# board.net
KiCad netlist of a schematic drawn in EAGLE
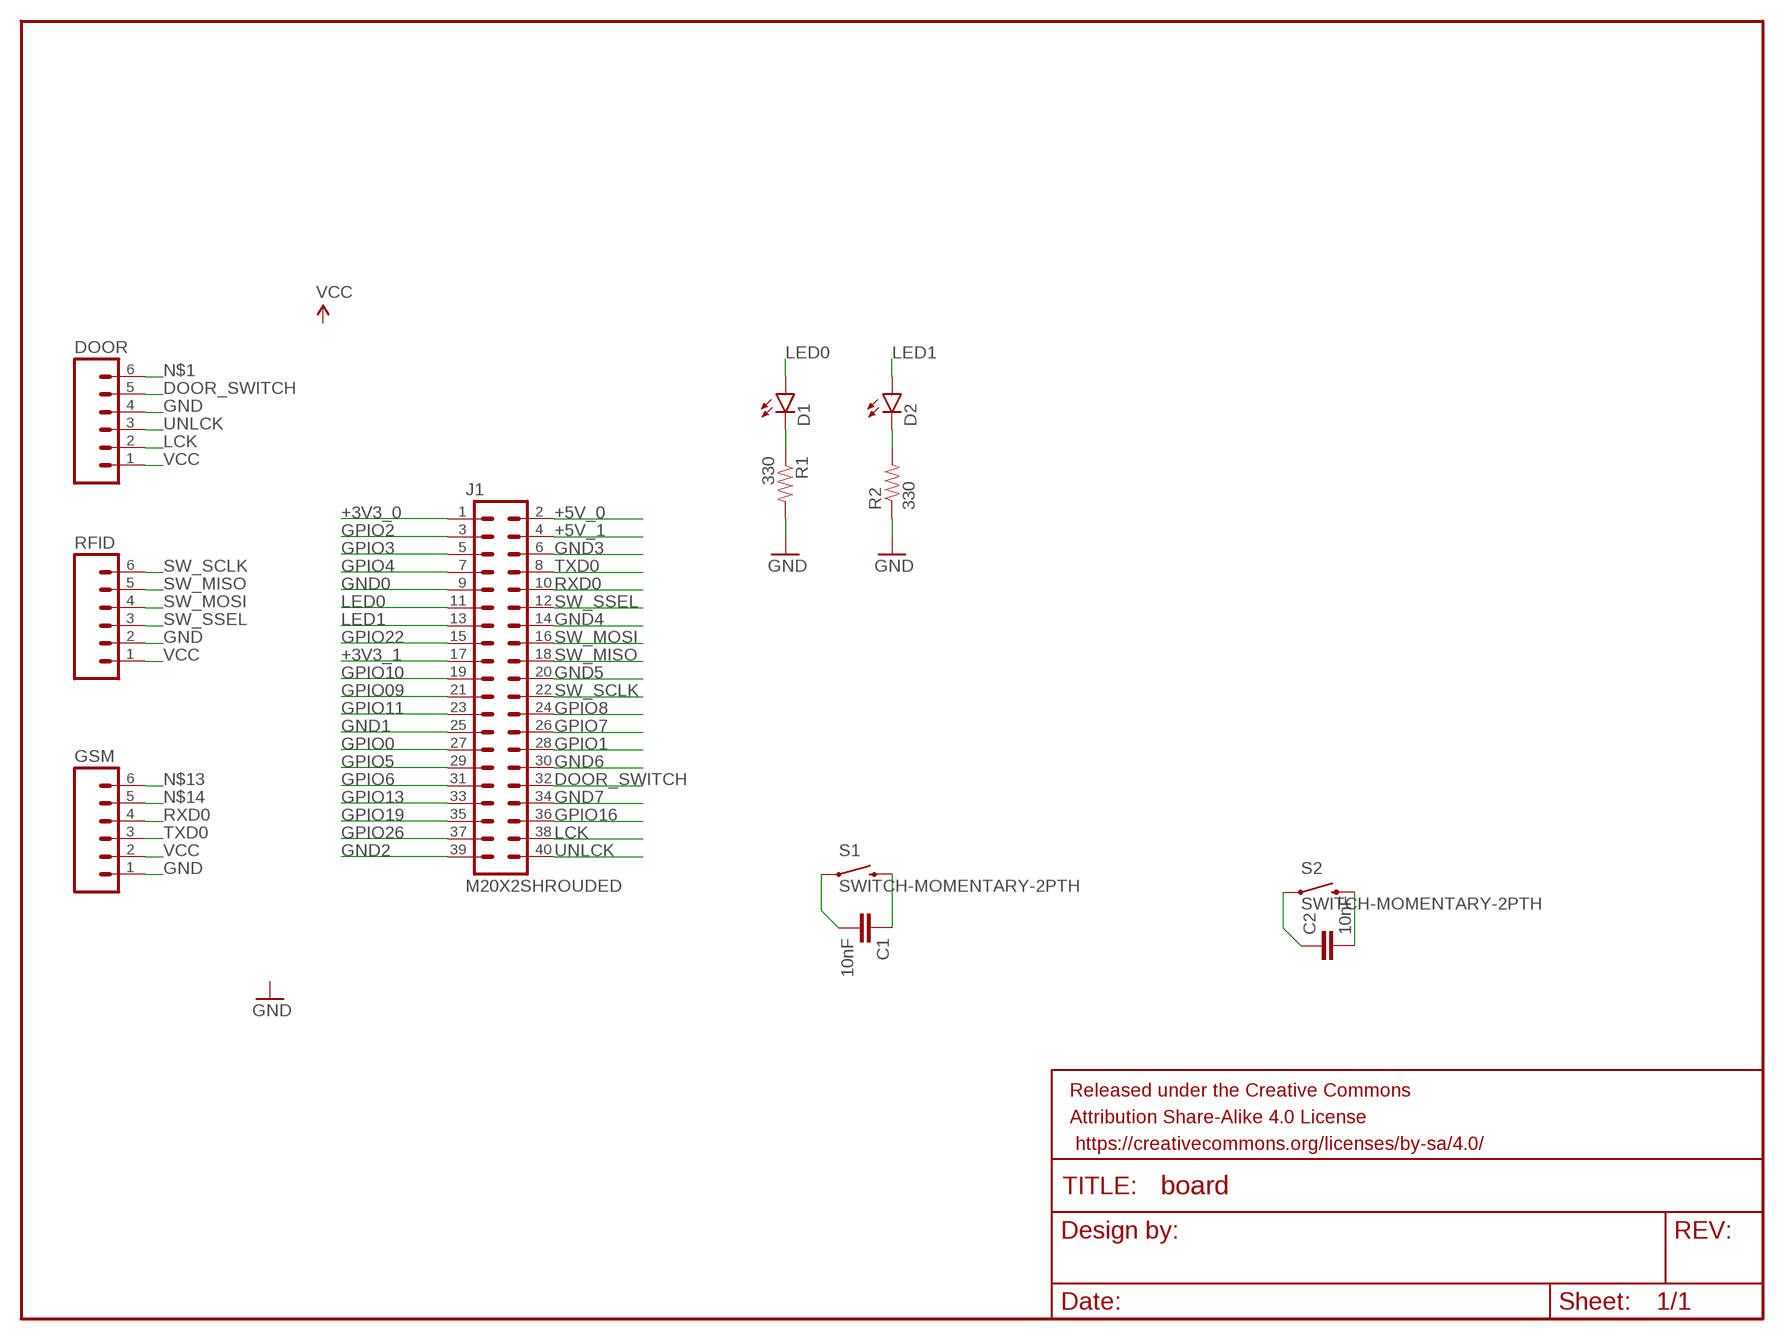
[diagram p0: schematic, sheet 1]

(export (version "E")
  (design (tool "Eeschema 10.0.6"))
  (components
    (comp (ref "C1")
      (value "10nF")
      (footprint "eagle-import:CAP-PTH-SMALL")
      (libsource (lib "eagle-import") (part "CAPPTH"))
    )
    (comp (ref "C2")
      (value "10nF")
      (footprint "eagle-import:CAP-PTH-SMALL")
      (libsource (lib "eagle-import") (part "CAPPTH"))
    )
    (comp (ref "D1")
      (value "LED5MM")
      (footprint "eagle-import:LED5MM")
      (libsource (lib "eagle-import") (part "LED5MM"))
    )
    (comp (ref "D2")
      (value "LED5MM")
      (footprint "eagle-import:LED5MM")
      (libsource (lib "eagle-import") (part "LED5MM"))
    )
    (comp (ref "DOOR")
      (value "M06LOCK")
      (footprint "eagle-import:1X06_LOCK")
      (libsource (lib "eagle-import") (part "M06LOCK"))
    )
    (comp (ref "FRAME1")
      (value "FRAME-LETTER")
      (footprint "eagle-import:CREATIVE_COMMONS")
      (libsource (lib "eagle-import") (part "FRAME-LETTER"))
    )
    (comp (ref "GSM")
      (value "M06LOCK")
      (footprint "eagle-import:1X06_LOCK")
      (libsource (lib "eagle-import") (part "M06LOCK"))
    )
    (comp (ref "J1")
      (value "M20X2SHROUDED")
      (footprint "eagle-import:2X20_SHROUDED")
      (libsource (lib "eagle-import") (part "M20X2SHROUDED"))
    )
    (comp (ref "R1")
      (value "330")
      (footprint "eagle-import:AXIAL-0.4")
      (libsource (lib "eagle-import") (part "RESISTORPTH-1/4W"))
    )
    (comp (ref "R2")
      (value "330")
      (footprint "eagle-import:AXIAL-0.4")
      (libsource (lib "eagle-import") (part "RESISTORPTH-1/4W"))
    )
    (comp (ref "RFID")
      (value "M06LOCK")
      (footprint "eagle-import:1X06_LOCK")
      (libsource (lib "eagle-import") (part "M06LOCK"))
    )
    (comp (ref "S1")
      (value "SWITCH-MOMENTARY-2PTH")
      (footprint "eagle-import:TACTILE-PTH")
      (libsource (lib "eagle-import") (part "SWITCH-MOMENTARY-2PTH"))
    )
    (comp (ref "S2")
      (value "SWITCH-MOMENTARY-2PTH")
      (footprint "eagle-import:TACTILE-PTH")
      (libsource (lib "eagle-import") (part "SWITCH-MOMENTARY-2PTH"))
    )
  )
  (nets
    (net (code "1") (name "/+3V3_0") (class "Default")
      (node (ref "J1") (pin "1") (pinfunction "1_1") (pintype "passive"))
    )
    (net (code "2") (name "/+3V3_1") (class "Default")
      (node (ref "J1") (pin "17") (pinfunction "17_17") (pintype "passive"))
    )
    (net (code "3") (name "/+5V_0") (class "Default")
      (node (ref "J1") (pin "2") (pinfunction "2_2") (pintype "passive"))
    )
    (net (code "4") (name "/+5V_1") (class "Default")
      (node (ref "J1") (pin "4") (pinfunction "4_4") (pintype "passive"))
    )
    (net (code "5") (name "/DOOR_SWITCH") (class "Default")
      (node (ref "DOOR") (pin "5") (pinfunction "5_5") (pintype "passive"))
      (node (ref "J1") (pin "32") (pinfunction "32_32") (pintype "passive"))
    )
    (net (code "6") (name "/GND0") (class "Default")
      (node (ref "J1") (pin "9") (pinfunction "9_9") (pintype "passive"))
    )
    (net (code "7") (name "/GND1") (class "Default")
      (node (ref "J1") (pin "25") (pinfunction "25_25") (pintype "passive"))
    )
    (net (code "8") (name "/GND2") (class "Default")
      (node (ref "J1") (pin "39") (pinfunction "39_39") (pintype "passive"))
    )
    (net (code "9") (name "/GND3") (class "Default")
      (node (ref "J1") (pin "6") (pinfunction "6_6") (pintype "passive"))
    )
    (net (code "10") (name "/GND4") (class "Default")
      (node (ref "J1") (pin "14") (pinfunction "14_14") (pintype "passive"))
    )
    (net (code "11") (name "/GND5") (class "Default")
      (node (ref "J1") (pin "20") (pinfunction "20_20") (pintype "passive"))
    )
    (net (code "12") (name "/GND6") (class "Default")
      (node (ref "J1") (pin "30") (pinfunction "30_30") (pintype "passive"))
    )
    (net (code "13") (name "/GND7") (class "Default")
      (node (ref "J1") (pin "34") (pinfunction "34_34") (pintype "passive"))
    )
    (net (code "14") (name "/GPIO0") (class "Default")
      (node (ref "J1") (pin "27") (pinfunction "27_27") (pintype "passive"))
    )
    (net (code "15") (name "/GPIO1") (class "Default")
      (node (ref "J1") (pin "28") (pinfunction "28_28") (pintype "passive"))
    )
    (net (code "16") (name "/GPIO2") (class "Default")
      (node (ref "J1") (pin "3") (pinfunction "3_3") (pintype "passive"))
    )
    (net (code "17") (name "/GPIO3") (class "Default")
      (node (ref "J1") (pin "5") (pinfunction "5_5") (pintype "passive"))
    )
    (net (code "18") (name "/GPIO4") (class "Default")
      (node (ref "J1") (pin "7") (pinfunction "7_7") (pintype "passive"))
    )
    (net (code "19") (name "/GPIO5") (class "Default")
      (node (ref "J1") (pin "29") (pinfunction "29_29") (pintype "passive"))
    )
    (net (code "20") (name "/GPIO6") (class "Default")
      (node (ref "J1") (pin "31") (pinfunction "31_31") (pintype "passive"))
    )
    (net (code "21") (name "/GPIO7") (class "Default")
      (node (ref "J1") (pin "26") (pinfunction "26_26") (pintype "passive"))
    )
    (net (code "22") (name "/GPIO8") (class "Default")
      (node (ref "J1") (pin "24") (pinfunction "24_24") (pintype "passive"))
    )
    (net (code "23") (name "/GPIO09") (class "Default")
      (node (ref "J1") (pin "21") (pinfunction "21_21") (pintype "passive"))
    )
    (net (code "24") (name "/GPIO10") (class "Default")
      (node (ref "J1") (pin "19") (pinfunction "19_19") (pintype "passive"))
    )
    (net (code "25") (name "/GPIO11") (class "Default")
      (node (ref "J1") (pin "23") (pinfunction "23_23") (pintype "passive"))
    )
    (net (code "26") (name "/GPIO13") (class "Default")
      (node (ref "J1") (pin "33") (pinfunction "33_33") (pintype "passive"))
    )
    (net (code "27") (name "/GPIO16") (class "Default")
      (node (ref "J1") (pin "36") (pinfunction "36_36") (pintype "passive"))
    )
    (net (code "28") (name "/GPIO19") (class "Default")
      (node (ref "J1") (pin "35") (pinfunction "35_35") (pintype "passive"))
    )
    (net (code "29") (name "/GPIO22") (class "Default")
      (node (ref "J1") (pin "15") (pinfunction "15_15") (pintype "passive"))
    )
    (net (code "30") (name "/GPIO26") (class "Default")
      (node (ref "J1") (pin "37") (pinfunction "37_37") (pintype "passive"))
    )
    (net (code "31") (name "/LCK") (class "Default")
      (node (ref "DOOR") (pin "2") (pinfunction "2_2") (pintype "passive"))
      (node (ref "J1") (pin "38") (pinfunction "38_38") (pintype "passive"))
    )
    (net (code "32") (name "/LED0") (class "Default")
      (node (ref "D1") (pin "A") (pinfunction "A_A") (pintype "passive"))
      (node (ref "J1") (pin "11") (pinfunction "11_11") (pintype "passive"))
    )
    (net (code "33") (name "/LED1") (class "Default")
      (node (ref "D2") (pin "A") (pinfunction "A_A") (pintype "passive"))
      (node (ref "J1") (pin "13") (pinfunction "13_13") (pintype "passive"))
    )
    (net (code "34") (name "/N$1") (class "Default")
      (node (ref "DOOR") (pin "6") (pinfunction "6_6") (pintype "passive"))
    )
    (net (code "35") (name "/N$13") (class "Default")
      (node (ref "GSM") (pin "6") (pinfunction "6_6") (pintype "passive"))
    )
    (net (code "36") (name "/N$14") (class "Default")
      (node (ref "GSM") (pin "5") (pinfunction "5_5") (pintype "passive"))
    )
    (net (code "37") (name "/RXD0") (class "Default")
      (node (ref "GSM") (pin "4") (pinfunction "4_4") (pintype "passive"))
      (node (ref "J1") (pin "10") (pinfunction "10_10") (pintype "passive"))
    )
    (net (code "38") (name "/SW_MISO") (class "Default")
      (node (ref "J1") (pin "18") (pinfunction "18_18") (pintype "passive"))
      (node (ref "RFID") (pin "5") (pinfunction "5_5") (pintype "passive"))
    )
    (net (code "39") (name "/SW_MOSI") (class "Default")
      (node (ref "J1") (pin "16") (pinfunction "16_16") (pintype "passive"))
      (node (ref "RFID") (pin "4") (pinfunction "4_4") (pintype "passive"))
    )
    (net (code "40") (name "/SW_SCLK") (class "Default")
      (node (ref "J1") (pin "22") (pinfunction "22_22") (pintype "passive"))
      (node (ref "RFID") (pin "6") (pinfunction "6_6") (pintype "passive"))
    )
    (net (code "41") (name "/SW_SSEL") (class "Default")
      (node (ref "J1") (pin "12") (pinfunction "12_12") (pintype "passive"))
      (node (ref "RFID") (pin "3") (pinfunction "3_3") (pintype "passive"))
    )
    (net (code "42") (name "/TXD0") (class "Default")
      (node (ref "GSM") (pin "3") (pinfunction "3_3") (pintype "passive"))
      (node (ref "J1") (pin "8") (pinfunction "8_8") (pintype "passive"))
    )
    (net (code "43") (name "/UNLCK") (class "Default")
      (node (ref "DOOR") (pin "3") (pinfunction "3_3") (pintype "passive"))
      (node (ref "J1") (pin "40") (pinfunction "40_40") (pintype "passive"))
    )
    (net (code "44") (name "GND") (class "Default")
      (node (ref "DOOR") (pin "4") (pinfunction "4_4") (pintype "passive"))
      (node (ref "GSM") (pin "1") (pinfunction "1_1") (pintype "passive"))
      (node (ref "R1") (pin "P$2") (pinfunction "2_P$2") (pintype "passive"))
      (node (ref "R2") (pin "P$1") (pinfunction "1_P$1") (pintype "passive"))
      (node (ref "RFID") (pin "2") (pinfunction "2_2") (pintype "passive"))
    )
    (net (code "45") (name "Net-(C1-Pad2)") (class "Default")
      (node (ref "C1") (pin "2") (pinfunction "2_2") (pintype "passive"))
      (node (ref "S1") (pin "1") (pinfunction "1_1") (pintype "passive"))
    )
    (net (code "46") (name "Net-(C2-Pad1)") (class "Default")
      (node (ref "C2") (pin "1") (pinfunction "1_1") (pintype "passive"))
      (node (ref "S2") (pin "1") (pinfunction "1_1") (pintype "passive"))
    )
    (net (code "47") (name "Net-(D1-C)") (class "Default")
      (node (ref "D1") (pin "K") (pinfunction "C_K") (pintype "passive"))
      (node (ref "R1") (pin "P$1") (pinfunction "1_P$1") (pintype "passive"))
    )
    (net (code "48") (name "Net-(D2-C)") (class "Default")
      (node (ref "D2") (pin "K") (pinfunction "C_K") (pintype "passive"))
      (node (ref "R2") (pin "P$2") (pinfunction "2_P$2") (pintype "passive"))
    )
    (net (code "49") (name "Net-(S1-2)") (class "Default")
      (node (ref "C1") (pin "1") (pinfunction "1_1") (pintype "passive"))
      (node (ref "S1") (pin "3") (pinfunction "2_3") (pintype "passive"))
    )
    (net (code "50") (name "Net-(S2-2)") (class "Default")
      (node (ref "C2") (pin "2") (pinfunction "2_2") (pintype "passive"))
      (node (ref "S2") (pin "3") (pinfunction "2_3") (pintype "passive"))
    )
    (net (code "51") (name "VCC") (class "Default")
      (node (ref "DOOR") (pin "1") (pinfunction "1_1") (pintype "passive"))
      (node (ref "GSM") (pin "2") (pinfunction "2_2") (pintype "passive"))
      (node (ref "RFID") (pin "1") (pinfunction "1_1") (pintype "passive"))
    )
  )
)
